# sch_substrate_board_motor_driver.net
KiCad netlist of a schematic drawn in Altium Designer
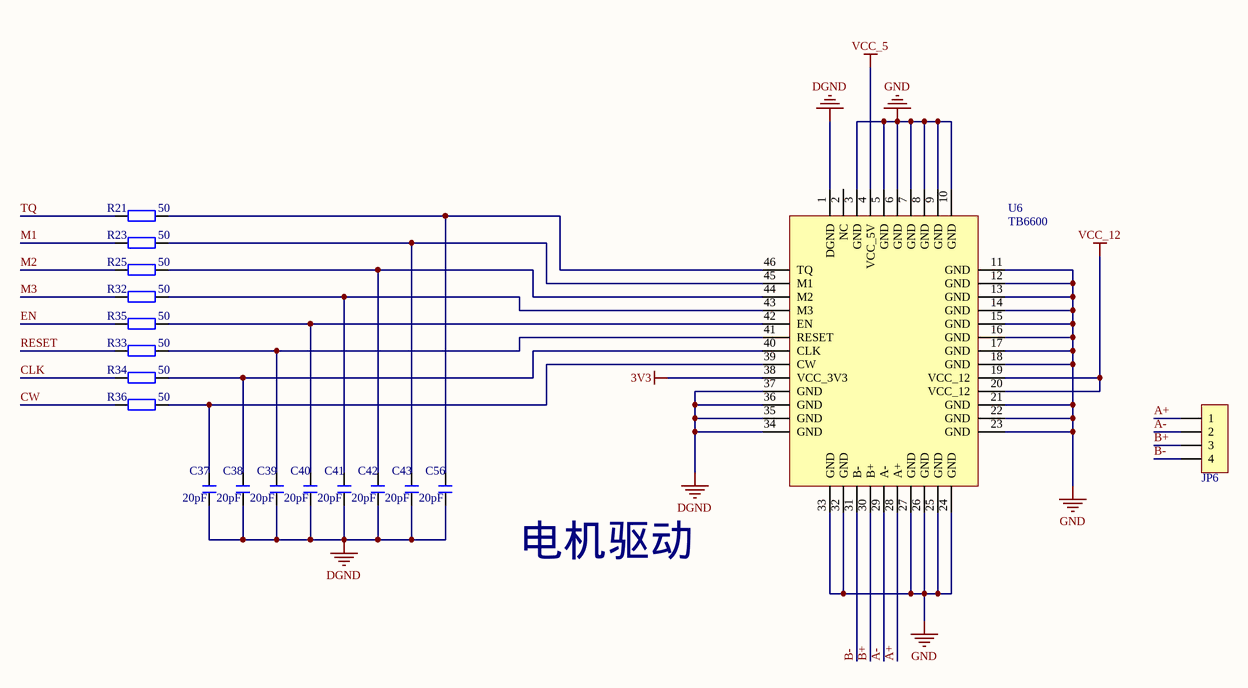
[diagram p0: sch_substrate_board_motor_driver.SchDoc]

(export (version "E")
  (design (tool "Eeschema 10.0.6"))
  (components
    (comp (ref "C37")
      (value "20pF")
      (footprint "C 0805_L")
      (description "贴片电容")
      (libsource (lib "0.1 - 电阻-电容-电感") (part "C"))
    )
    (comp (ref "C38")
      (value "20pF")
      (footprint "C 0805_L")
      (description "贴片电容")
      (libsource (lib "0.1 - 电阻-电容-电感") (part "C"))
    )
    (comp (ref "C39")
      (value "20pF")
      (footprint "C 0805_L")
      (description "贴片电容")
      (libsource (lib "0.1 - 电阻-电容-电感") (part "C"))
    )
    (comp (ref "C40")
      (value "20pF")
      (footprint "C 0805_L")
      (description "贴片电容")
      (libsource (lib "0.1 - 电阻-电容-电感") (part "C"))
    )
    (comp (ref "C41")
      (value "20pF")
      (footprint "C 0805_L")
      (description "贴片电容")
      (libsource (lib "0.1 - 电阻-电容-电感") (part "C"))
    )
    (comp (ref "C42")
      (value "20pF")
      (footprint "C 0805_L")
      (description "贴片电容")
      (libsource (lib "0.1 - 电阻-电容-电感") (part "C"))
    )
    (comp (ref "C43")
      (value "20pF")
      (footprint "C 0805_L")
      (description "贴片电容")
      (libsource (lib "0.1 - 电阻-电容-电感") (part "C"))
    )
    (comp (ref "C56")
      (value "20pF")
      (footprint "C 0805_L")
      (description "贴片电容")
      (libsource (lib "0.1 - 电阻-电容-电感") (part "C"))
    )
    (comp (ref "JP6")
      (value "HDR-1X4")
      (footprint "KF128-3.81-4P")
      (description "4P接插件")
      (fields (field (name "版权归属") "封装库来自淘宝 ID：黄晶宝石"))
      (libsource (lib "5.6 - 接插件-脚距3.81 (150mil) ") (part "Header 4"))
    )
    (comp (ref "R21")
      (value "50")
      (footprint "R 0805_L")
      (description "贴片电阻")
      (fields (field (name "版权归属") "来自淘宝 ID：黄晶宝石"))
      (libsource (lib "0.1 - 电阻-电容-电感") (part "R"))
    )
    (comp (ref "R23")
      (value "50")
      (footprint "R 0805_L")
      (description "贴片电阻")
      (fields (field (name "版权归属") "来自淘宝 ID：黄晶宝石"))
      (libsource (lib "0.1 - 电阻-电容-电感") (part "R"))
    )
    (comp (ref "R25")
      (value "50")
      (footprint "R 0805_L")
      (description "贴片电阻")
      (fields (field (name "版权归属") "来自淘宝 ID：黄晶宝石"))
      (libsource (lib "0.1 - 电阻-电容-电感") (part "R"))
    )
    (comp (ref "R32")
      (value "50")
      (footprint "R 0805_L")
      (description "贴片电阻")
      (fields (field (name "版权归属") "来自淘宝 ID：黄晶宝石"))
      (libsource (lib "0.1 - 电阻-电容-电感") (part "R"))
    )
    (comp (ref "R33")
      (value "50")
      (footprint "R 0805_L")
      (description "贴片电阻")
      (fields (field (name "版权归属") "来自淘宝 ID：黄晶宝石"))
      (libsource (lib "0.1 - 电阻-电容-电感") (part "R"))
    )
    (comp (ref "R34")
      (value "50")
      (footprint "R 0805_L")
      (description "贴片电阻")
      (fields (field (name "版权归属") "来自淘宝 ID：黄晶宝石"))
      (libsource (lib "0.1 - 电阻-电容-电感") (part "R"))
    )
    (comp (ref "R35")
      (value "50")
      (footprint "R 0805_L")
      (description "贴片电阻")
      (fields (field (name "版权归属") "来自淘宝 ID：黄晶宝石"))
      (libsource (lib "0.1 - 电阻-电容-电感") (part "R"))
    )
    (comp (ref "R36")
      (value "50")
      (footprint "R 0805_L")
      (description "贴片电阻")
      (fields (field (name "版权归属") "来自淘宝 ID：黄晶宝石"))
      (libsource (lib "0.1 - 电阻-电容-电感") (part "R"))
    )
    (comp (ref "U6")
      (value "TB6600")
      (footprint "motor_drive_V2.0")
      (description "电机驱动板")
      (libsource (lib "schlib_substrate") (part "Motor_Drive_V2.0"))
    )
  )
  (nets
    (net (code "1") (name "/A+") (class "Default")
      (node (ref "JP6") (pin "1") (pinfunction "1_1") (pintype "passive"))
      (node (ref "U6") (pin "28") (pinfunction "A+_28") (pintype "passive"))
    )
    (net (code "2") (name "/A-") (class "Default")
      (node (ref "JP6") (pin "2") (pinfunction "2_2") (pintype "passive"))
      (node (ref "U6") (pin "29") (pinfunction "A-_29") (pintype "passive"))
    )
    (net (code "3") (name "/B+") (class "Default")
      (node (ref "JP6") (pin "3") (pinfunction "3_3") (pintype "passive"))
      (node (ref "U6") (pin "30") (pinfunction "B+_30") (pintype "passive"))
    )
    (net (code "4") (name "/B-") (class "Default")
      (node (ref "JP6") (pin "4") (pinfunction "4_4") (pintype "passive"))
      (node (ref "U6") (pin "31") (pinfunction "B-_31") (pintype "passive"))
    )
    (net (code "5") (name "/CLK") (class "Default")
      (node (ref "R34") (pin "1") (pinfunction "1_1") (pintype "passive"))
    )
    (net (code "6") (name "/CW") (class "Default")
      (node (ref "R36") (pin "1") (pinfunction "1_1") (pintype "passive"))
    )
    (net (code "7") (name "/EN") (class "Default")
      (node (ref "R35") (pin "1") (pinfunction "1_1") (pintype "passive"))
    )
    (net (code "8") (name "/M1") (class "Default")
      (node (ref "R23") (pin "1") (pinfunction "1_1") (pintype "passive"))
    )
    (net (code "9") (name "/M2") (class "Default")
      (node (ref "R25") (pin "1") (pinfunction "1_1") (pintype "passive"))
    )
    (net (code "10") (name "/M3") (class "Default")
      (node (ref "R32") (pin "1") (pinfunction "1_1") (pintype "passive"))
    )
    (net (code "11") (name "/RESET") (class "Default")
      (node (ref "R33") (pin "1") (pinfunction "1_1") (pintype "passive"))
    )
    (net (code "12") (name "/TQ") (class "Default")
      (node (ref "R21") (pin "1") (pinfunction "1_1") (pintype "passive"))
    )
    (net (code "13") (name "3V3") (class "Default")
      (node (ref "U6") (pin "38") (pinfunction "VCC_3V3_38") (pintype "passive"))
    )
    (net (code "14") (name "DGND") (class "Default")
      (node (ref "C37") (pin "1") (pinfunction "1_1") (pintype "passive"))
      (node (ref "C38") (pin "1") (pinfunction "1_1") (pintype "passive"))
      (node (ref "C39") (pin "1") (pinfunction "1_1") (pintype "passive"))
      (node (ref "C40") (pin "1") (pinfunction "1_1") (pintype "passive"))
      (node (ref "C41") (pin "1") (pinfunction "1_1") (pintype "passive"))
      (node (ref "C42") (pin "1") (pinfunction "1_1") (pintype "passive"))
      (node (ref "C43") (pin "1") (pinfunction "1_1") (pintype "passive"))
      (node (ref "C56") (pin "1") (pinfunction "1_1") (pintype "passive"))
      (node (ref "U6") (pin "1") (pinfunction "DGND_1") (pintype "passive"))
      (node (ref "U6") (pin "34") (pinfunction "GND_34") (pintype "passive"))
      (node (ref "U6") (pin "35") (pinfunction "GND_35") (pintype "passive"))
      (node (ref "U6") (pin "36") (pinfunction "GND_36") (pintype "passive"))
      (node (ref "U6") (pin "37") (pinfunction "GND_37") (pintype "passive"))
    )
    (net (code "15") (name "GND") (class "Default")
      (node (ref "U6") (pin "10") (pinfunction "GND_10") (pintype "passive"))
      (node (ref "U6") (pin "11") (pinfunction "GND_11") (pintype "passive"))
      (node (ref "U6") (pin "12") (pinfunction "GND_12") (pintype "passive"))
      (node (ref "U6") (pin "13") (pinfunction "GND_13") (pintype "passive"))
      (node (ref "U6") (pin "14") (pinfunction "GND_14") (pintype "passive"))
      (node (ref "U6") (pin "15") (pinfunction "GND_15") (pintype "passive"))
      (node (ref "U6") (pin "16") (pinfunction "GND_16") (pintype "passive"))
      (node (ref "U6") (pin "17") (pinfunction "GND_17") (pintype "passive"))
      (node (ref "U6") (pin "18") (pinfunction "GND_18") (pintype "passive"))
      (node (ref "U6") (pin "21") (pinfunction "GND_21") (pintype "passive"))
      (node (ref "U6") (pin "22") (pinfunction "GND_22") (pintype "passive"))
      (node (ref "U6") (pin "23") (pinfunction "GND_23") (pintype "passive"))
      (node (ref "U6") (pin "24") (pinfunction "GND_24") (pintype "passive"))
      (node (ref "U6") (pin "25") (pinfunction "GND_25") (pintype "passive"))
      (node (ref "U6") (pin "26") (pinfunction "GND_26") (pintype "passive"))
      (node (ref "U6") (pin "27") (pinfunction "GND_27") (pintype "passive"))
      (node (ref "U6") (pin "3") (pinfunction "GND_3") (pintype "passive"))
      (node (ref "U6") (pin "32") (pinfunction "GND_32") (pintype "passive"))
      (node (ref "U6") (pin "33") (pinfunction "GND_33") (pintype "passive"))
      (node (ref "U6") (pin "5") (pinfunction "GND_5") (pintype "passive"))
      (node (ref "U6") (pin "6") (pinfunction "GND_6") (pintype "passive"))
      (node (ref "U6") (pin "7") (pinfunction "GND_7") (pintype "passive"))
      (node (ref "U6") (pin "8") (pinfunction "GND_8") (pintype "passive"))
      (node (ref "U6") (pin "9") (pinfunction "GND_9") (pintype "passive"))
    )
    (net (code "16") (name "Net-(U6-CLK)") (class "Default")
      (node (ref "C38") (pin "2") (pinfunction "2_2") (pintype "passive"))
      (node (ref "R34") (pin "2") (pinfunction "2_2") (pintype "passive"))
      (node (ref "U6") (pin "40") (pinfunction "CLK_40") (pintype "passive"))
    )
    (net (code "17") (name "Net-(U6-CW)") (class "Default")
      (node (ref "C37") (pin "2") (pinfunction "2_2") (pintype "passive"))
      (node (ref "R36") (pin "2") (pinfunction "2_2") (pintype "passive"))
      (node (ref "U6") (pin "39") (pinfunction "CW_39") (pintype "passive"))
    )
    (net (code "18") (name "Net-(U6-EN)") (class "Default")
      (node (ref "C40") (pin "2") (pinfunction "2_2") (pintype "passive"))
      (node (ref "R35") (pin "2") (pinfunction "2_2") (pintype "passive"))
      (node (ref "U6") (pin "42") (pinfunction "EN_42") (pintype "passive"))
    )
    (net (code "19") (name "Net-(U6-M1)") (class "Default")
      (node (ref "C43") (pin "2") (pinfunction "2_2") (pintype "passive"))
      (node (ref "R23") (pin "2") (pinfunction "2_2") (pintype "passive"))
      (node (ref "U6") (pin "45") (pinfunction "M1_45") (pintype "passive"))
    )
    (net (code "20") (name "Net-(U6-M2)") (class "Default")
      (node (ref "C42") (pin "2") (pinfunction "2_2") (pintype "passive"))
      (node (ref "R25") (pin "2") (pinfunction "2_2") (pintype "passive"))
      (node (ref "U6") (pin "44") (pinfunction "M2_44") (pintype "passive"))
    )
    (net (code "21") (name "Net-(U6-M3)") (class "Default")
      (node (ref "C41") (pin "2") (pinfunction "2_2") (pintype "passive"))
      (node (ref "R32") (pin "2") (pinfunction "2_2") (pintype "passive"))
      (node (ref "U6") (pin "43") (pinfunction "M3_43") (pintype "passive"))
    )
    (net (code "22") (name "Net-(U6-RESET)") (class "Default")
      (node (ref "C39") (pin "2") (pinfunction "2_2") (pintype "passive"))
      (node (ref "R33") (pin "2") (pinfunction "2_2") (pintype "passive"))
      (node (ref "U6") (pin "41") (pinfunction "RESET_41") (pintype "passive"))
    )
    (net (code "23") (name "Net-(U6-TQ)") (class "Default")
      (node (ref "C56") (pin "2") (pinfunction "2_2") (pintype "passive"))
      (node (ref "R21") (pin "2") (pinfunction "2_2") (pintype "passive"))
      (node (ref "U6") (pin "46") (pinfunction "TQ_46") (pintype "passive"))
    )
    (net (code "24") (name "VCC_5") (class "Default")
      (node (ref "U6") (pin "4") (pinfunction "VCC_5V_4") (pintype "passive"))
    )
    (net (code "25") (name "VCC_12") (class "Default")
      (node (ref "U6") (pin "19") (pinfunction "VCC_12_19") (pintype "passive"))
      (node (ref "U6") (pin "20") (pinfunction "VCC_12_20") (pintype "passive"))
    )
    (net (code "26") (name "unconnected-(U6-NC-Pad2)") (class "Default")
      (node (ref "U6") (pin "2") (pinfunction "NC_2") (pintype "passive"))
    )
  )
)
